# v2.net
KiCad netlist of a schematic drawn in EAGLE
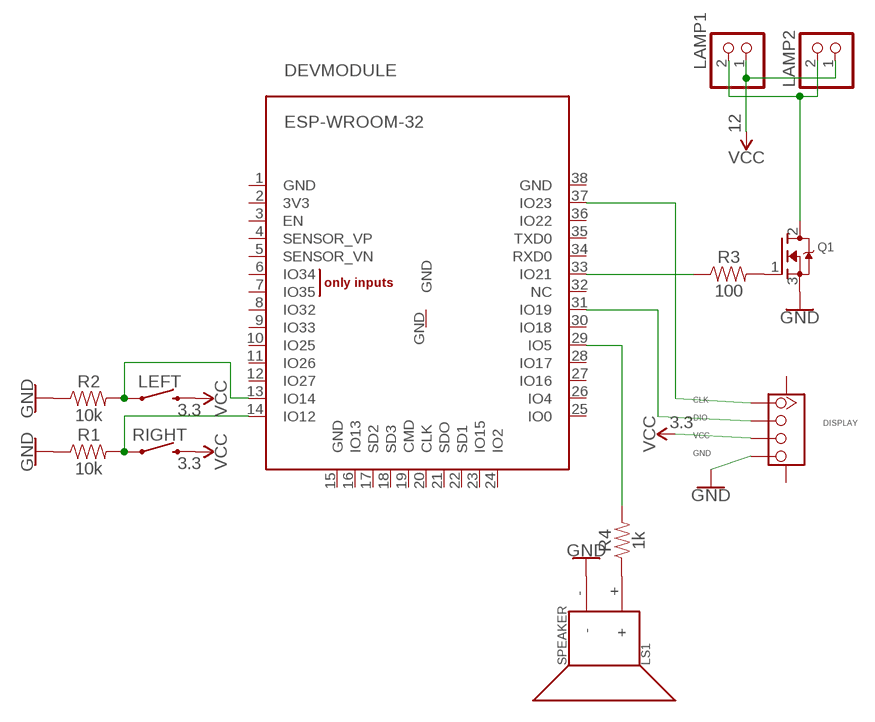
[diagram p0: schematic, sheet 1]

(export (version "E")
  (design (tool "Eeschema 10.0.6"))
  (components
    (comp (ref "DEVMODULE")
      (value "ESP-WROOM-32")
      (footprint "eagle-import:ESP-WROOM-32")
      (libsource (lib "eagle-import") (part "ESP-WROOM-32"))
    )
    (comp (ref "DISPLAY")
      (value "TWIG-4P-2.0-SMD-FEMALE-REINFORCE'90D'")
      (footprint "eagle-import:4P-SMD-2.0-90D")
      (libsource (lib "eagle-import") (part "TWIG-4P-2.0-SMD-FEMALE-REINFORCE'90D'"))
    )
    (comp (ref "LAMP1")
      (value "JST_2PIN-THM")
      (footprint "eagle-import:JST-PH-2-THM")
      (libsource (lib "eagle-import") (part "JST_2PIN-THM"))
    )
    (comp (ref "LAMP2")
      (value "JST_2PIN-THM")
      (footprint "eagle-import:JST-PH-2-THM")
      (libsource (lib "eagle-import") (part "JST_2PIN-THM"))
    )
    (comp (ref "LEFT")
      (value "MOMENTARY-SWITCH-SPST-PTH-6.0MM")
      (footprint "eagle-import:TACTILE_SWITCH_PTH_6.0MM")
      (fields (field (name "DIRECTION") "right"))
      (libsource (lib "eagle-import") (part "MOMENTARY-SWITCH-SPST-PTH-6.0MM"))
    )
    (comp (ref "LS1")
      (value "SPEAKER")
      (footprint "eagle-import:PCB_MOUNT_SPEAKER")
      (libsource (lib "eagle-import") (part "SPEAKER"))
    )
    (comp (ref "Q1")
      (value "MOSFET-NGDS_TO220V")
      (footprint "eagle-import:TO220V")
      (libsource (lib "eagle-import") (part "MOSFET-NGDS_TO220V"))
    )
    (comp (ref "R1")
      (value "10k")
      (footprint "eagle-import:0603")
      (libsource (lib "eagle-import") (part "10KOHM-0603-1/10W-1%"))
    )
    (comp (ref "R2")
      (value "10k")
      (footprint "eagle-import:0603")
      (libsource (lib "eagle-import") (part "10KOHM-0603-1/10W-1%"))
    )
    (comp (ref "R3")
      (value "100")
      (footprint "eagle-import:0603")
      (libsource (lib "eagle-import") (part "100OHM-0603-1/4W-5%"))
    )
    (comp (ref "R4")
      (value "1k")
      (footprint "eagle-import:AXIAL-0.3-KIT")
      (libsource (lib "eagle-import") (part "1KOHM-HORIZ_KIT-1/4W-1%"))
    )
    (comp (ref "RIGHT")
      (value "MOMENTARY-SWITCH-SPST-PTH-6.0MM")
      (footprint "eagle-import:TACTILE_SWITCH_PTH_6.0MM")
      (fields (field (name "DIRECTION") "right"))
      (libsource (lib "eagle-import") (part "MOMENTARY-SWITCH-SPST-PTH-6.0MM"))
    )
  )
  (nets
    (net (code "1") (name "/CLK") (class "Default")
      (node (ref "DEVMODULE") (pin "37") (pinfunction "IO23_37") (pintype "bidirectional"))
      (node (ref "DISPLAY") (pin "1") (pinfunction "1_1") (pintype "bidirectional"))
    )
    (net (code "2") (name "/DIO") (class "Default")
      (node (ref "DEVMODULE") (pin "31") (pinfunction "IO19_31") (pintype "bidirectional"))
      (node (ref "DISPLAY") (pin "2") (pinfunction "2_2") (pintype "bidirectional"))
    )
    (net (code "3") (name "GND") (class "Default")
      (node (ref "DISPLAY") (pin "4") (pinfunction "4_4") (pintype "bidirectional"))
      (node (ref "LS1") (pin "-") (pinfunction "-_-") (pintype "bidirectional"))
      (node (ref "Q1") (pin "3") (pinfunction "S_3") (pintype "bidirectional"))
      (node (ref "R1") (pin "1") (pinfunction "1_1") (pintype "passive"))
      (node (ref "R2") (pin "1") (pinfunction "1_1") (pintype "passive"))
    )
    (net (code "4") (name "Net-(DEVMODULE-IO5)") (class "Default")
      (node (ref "DEVMODULE") (pin "29") (pinfunction "IO5_29") (pintype "bidirectional"))
      (node (ref "R4") (pin "P$2") (pinfunction "2_P$2") (pintype "passive"))
    )
    (net (code "5") (name "Net-(DEVMODULE-IO12)") (class "Default")
      (node (ref "DEVMODULE") (pin "14") (pinfunction "IO12_14") (pintype "bidirectional"))
      (node (ref "R1") (pin "2") (pinfunction "2_2") (pintype "passive"))
      (node (ref "RIGHT") (pin "1") (pinfunction "1_1") (pintype "passive"))
    )
    (net (code "6") (name "Net-(DEVMODULE-IO14)") (class "Default")
      (node (ref "DEVMODULE") (pin "13") (pinfunction "IO14_13") (pintype "bidirectional"))
      (node (ref "LEFT") (pin "1") (pinfunction "1_1") (pintype "passive"))
      (node (ref "R2") (pin "2") (pinfunction "2_2") (pintype "passive"))
    )
    (net (code "7") (name "Net-(DEVMODULE-IO21)") (class "Default")
      (node (ref "DEVMODULE") (pin "33") (pinfunction "IO21_33") (pintype "bidirectional"))
      (node (ref "R3") (pin "1") (pinfunction "1_1") (pintype "passive"))
    )
    (net (code "8") (name "Net-(LAMP1-1)") (class "Default")
      (node (ref "LAMP1") (pin "2") (pinfunction "1_2") (pintype "passive"))
      (node (ref "LAMP2") (pin "2") (pinfunction "1_2") (pintype "passive"))
      (node (ref "Q1") (pin "2") (pinfunction "D_2") (pintype "bidirectional"))
    )
    (net (code "9") (name "Net-(Q1-G)") (class "Default")
      (node (ref "Q1") (pin "1") (pinfunction "G_1") (pintype "bidirectional"))
      (node (ref "R3") (pin "2") (pinfunction "2_2") (pintype "passive"))
    )
    (net (code "10") (name "Net-(R4-1)") (class "Default")
      (node (ref "LS1") (pin "+") (pinfunction "+_+") (pintype "bidirectional"))
      (node (ref "R4") (pin "P$1") (pinfunction "1_P$1") (pintype "passive"))
    )
    (net (code "11") (name "VCC") (class "Default")
      (node (ref "DISPLAY") (pin "3") (pinfunction "3_3") (pintype "bidirectional"))
      (node (ref "LAMP1") (pin "1") (pinfunction "2_1") (pintype "passive"))
      (node (ref "LAMP2") (pin "1") (pinfunction "2_1") (pintype "passive"))
      (node (ref "LEFT") (pin "3") (pinfunction "2_3") (pintype "passive"))
      (node (ref "RIGHT") (pin "3") (pinfunction "2_3") (pintype "passive"))
    )
    (net (code "12") (name "unconnected-(DEVMODULE-3V3-Pad2)") (class "Default")
      (node (ref "DEVMODULE") (pin "2") (pinfunction "3V3_2") (pintype "bidirectional"))
    )
    (net (code "13") (name "unconnected-(DEVMODULE-CLK-Pad20)") (class "Default")
      (node (ref "DEVMODULE") (pin "20") (pinfunction "CLK_20") (pintype "bidirectional"))
    )
    (net (code "14") (name "unconnected-(DEVMODULE-CMD-Pad19)") (class "Default")
      (node (ref "DEVMODULE") (pin "19") (pinfunction "CMD_19") (pintype "bidirectional"))
    )
    (net (code "15") (name "unconnected-(DEVMODULE-EN-Pad3)") (class "Default")
      (node (ref "DEVMODULE") (pin "3") (pinfunction "EN_3") (pintype "bidirectional"))
    )
    (net (code "16") (name "unconnected-(DEVMODULE-GND-Pad1)") (class "Default")
      (node (ref "DEVMODULE") (pin "1") (pinfunction "GND_1") (pintype "bidirectional"))
    )
    (net (code "17") (name "unconnected-(DEVMODULE-GND-Pad15)") (class "Default")
      (node (ref "DEVMODULE") (pin "15") (pinfunction "GND_15") (pintype "bidirectional"))
    )
    (net (code "18") (name "unconnected-(DEVMODULE-GND-Pad38)") (class "Default")
      (node (ref "DEVMODULE") (pin "38") (pinfunction "GND_38") (pintype "bidirectional"))
    )
    (net (code "19") (name "unconnected-(DEVMODULE-IO0-Pad25)") (class "Default")
      (node (ref "DEVMODULE") (pin "25") (pinfunction "IO0_25") (pintype "bidirectional"))
    )
    (net (code "20") (name "unconnected-(DEVMODULE-IO2-Pad24)") (class "Default")
      (node (ref "DEVMODULE") (pin "24") (pinfunction "IO2_24") (pintype "bidirectional"))
    )
    (net (code "21") (name "unconnected-(DEVMODULE-IO4-Pad26)") (class "Default")
      (node (ref "DEVMODULE") (pin "26") (pinfunction "IO4_26") (pintype "bidirectional"))
    )
    (net (code "22") (name "unconnected-(DEVMODULE-IO13-Pad16)") (class "Default")
      (node (ref "DEVMODULE") (pin "16") (pinfunction "IO13_16") (pintype "bidirectional"))
    )
    (net (code "23") (name "unconnected-(DEVMODULE-IO15-Pad23)") (class "Default")
      (node (ref "DEVMODULE") (pin "23") (pinfunction "IO15_23") (pintype "bidirectional"))
    )
    (net (code "24") (name "unconnected-(DEVMODULE-IO16-Pad27)") (class "Default")
      (node (ref "DEVMODULE") (pin "27") (pinfunction "IO16_27") (pintype "bidirectional"))
    )
    (net (code "25") (name "unconnected-(DEVMODULE-IO17-Pad28)") (class "Default")
      (node (ref "DEVMODULE") (pin "28") (pinfunction "IO17_28") (pintype "bidirectional"))
    )
    (net (code "26") (name "unconnected-(DEVMODULE-IO18-Pad30)") (class "Default")
      (node (ref "DEVMODULE") (pin "30") (pinfunction "IO18_30") (pintype "bidirectional"))
    )
    (net (code "27") (name "unconnected-(DEVMODULE-IO22-Pad36)") (class "Default")
      (node (ref "DEVMODULE") (pin "36") (pinfunction "IO22_36") (pintype "bidirectional"))
    )
    (net (code "28") (name "unconnected-(DEVMODULE-IO25-Pad10)") (class "Default")
      (node (ref "DEVMODULE") (pin "10") (pinfunction "IO25_10") (pintype "bidirectional"))
    )
    (net (code "29") (name "unconnected-(DEVMODULE-IO26-Pad11)") (class "Default")
      (node (ref "DEVMODULE") (pin "11") (pinfunction "IO26_11") (pintype "bidirectional"))
    )
    (net (code "30") (name "unconnected-(DEVMODULE-IO27-Pad12)") (class "Default")
      (node (ref "DEVMODULE") (pin "12") (pinfunction "IO27_12") (pintype "bidirectional"))
    )
    (net (code "31") (name "unconnected-(DEVMODULE-IO32-Pad8)") (class "Default")
      (node (ref "DEVMODULE") (pin "8") (pinfunction "IO32_8") (pintype "bidirectional"))
    )
    (net (code "32") (name "unconnected-(DEVMODULE-IO33-Pad9)") (class "Default")
      (node (ref "DEVMODULE") (pin "9") (pinfunction "IO33_9") (pintype "bidirectional"))
    )
    (net (code "33") (name "unconnected-(DEVMODULE-IO34-Pad6)") (class "Default")
      (node (ref "DEVMODULE") (pin "6") (pinfunction "IO34_6") (pintype "input"))
    )
    (net (code "34") (name "unconnected-(DEVMODULE-IO35-Pad7)") (class "Default")
      (node (ref "DEVMODULE") (pin "7") (pinfunction "IO35_7") (pintype "input"))
    )
    (net (code "35") (name "unconnected-(DEVMODULE-NC-Pad32)") (class "Default")
      (node (ref "DEVMODULE") (pin "32") (pinfunction "NC_32") (pintype "bidirectional"))
    )
    (net (code "36") (name "unconnected-(DEVMODULE-PadGND)") (class "Default")
      (node (ref "DEVMODULE") (pin "GND") (pinfunction "GND_GND") (pintype "bidirectional"))
    )
    (net (code "37") (name "unconnected-(DEVMODULE-RXD0-Pad34)") (class "Default")
      (node (ref "DEVMODULE") (pin "34") (pinfunction "RXD0_34") (pintype "bidirectional"))
    )
    (net (code "38") (name "unconnected-(DEVMODULE-SD1-Pad22)") (class "Default")
      (node (ref "DEVMODULE") (pin "22") (pinfunction "SD1_22") (pintype "bidirectional"))
    )
    (net (code "39") (name "unconnected-(DEVMODULE-SD2-Pad17)") (class "Default")
      (node (ref "DEVMODULE") (pin "17") (pinfunction "SD2_17") (pintype "bidirectional"))
    )
    (net (code "40") (name "unconnected-(DEVMODULE-SD3-Pad18)") (class "Default")
      (node (ref "DEVMODULE") (pin "18") (pinfunction "SD3_18") (pintype "bidirectional"))
    )
    (net (code "41") (name "unconnected-(DEVMODULE-SDO-Pad21)") (class "Default")
      (node (ref "DEVMODULE") (pin "21") (pinfunction "SDO_21") (pintype "bidirectional"))
    )
    (net (code "42") (name "unconnected-(DEVMODULE-SENSOR_VN-Pad5)") (class "Default")
      (node (ref "DEVMODULE") (pin "5") (pinfunction "SENSOR_VN_5") (pintype "input"))
    )
    (net (code "43") (name "unconnected-(DEVMODULE-SENSOR_VP-Pad4)") (class "Default")
      (node (ref "DEVMODULE") (pin "4") (pinfunction "SENSOR_VP_4") (pintype "input"))
    )
    (net (code "44") (name "unconnected-(DEVMODULE-TXD0-Pad35)") (class "Default")
      (node (ref "DEVMODULE") (pin "35") (pinfunction "TXD0_35") (pintype "bidirectional"))
    )
    (net (code "45") (name "unconnected-(DISPLAY-PadSS1)") (class "Default")
      (node (ref "DISPLAY") (pin "SS1") (pinfunction "SS1_SS1") (pintype "bidirectional"))
    )
    (net (code "46") (name "unconnected-(DISPLAY-PadSS2)") (class "Default")
      (node (ref "DISPLAY") (pin "SS2") (pinfunction "SS2_SS2") (pintype "bidirectional"))
    )
  )
)
